# non_inv_high_pass_filter.net
KiCad netlist of a schematic drawn in EAGLE
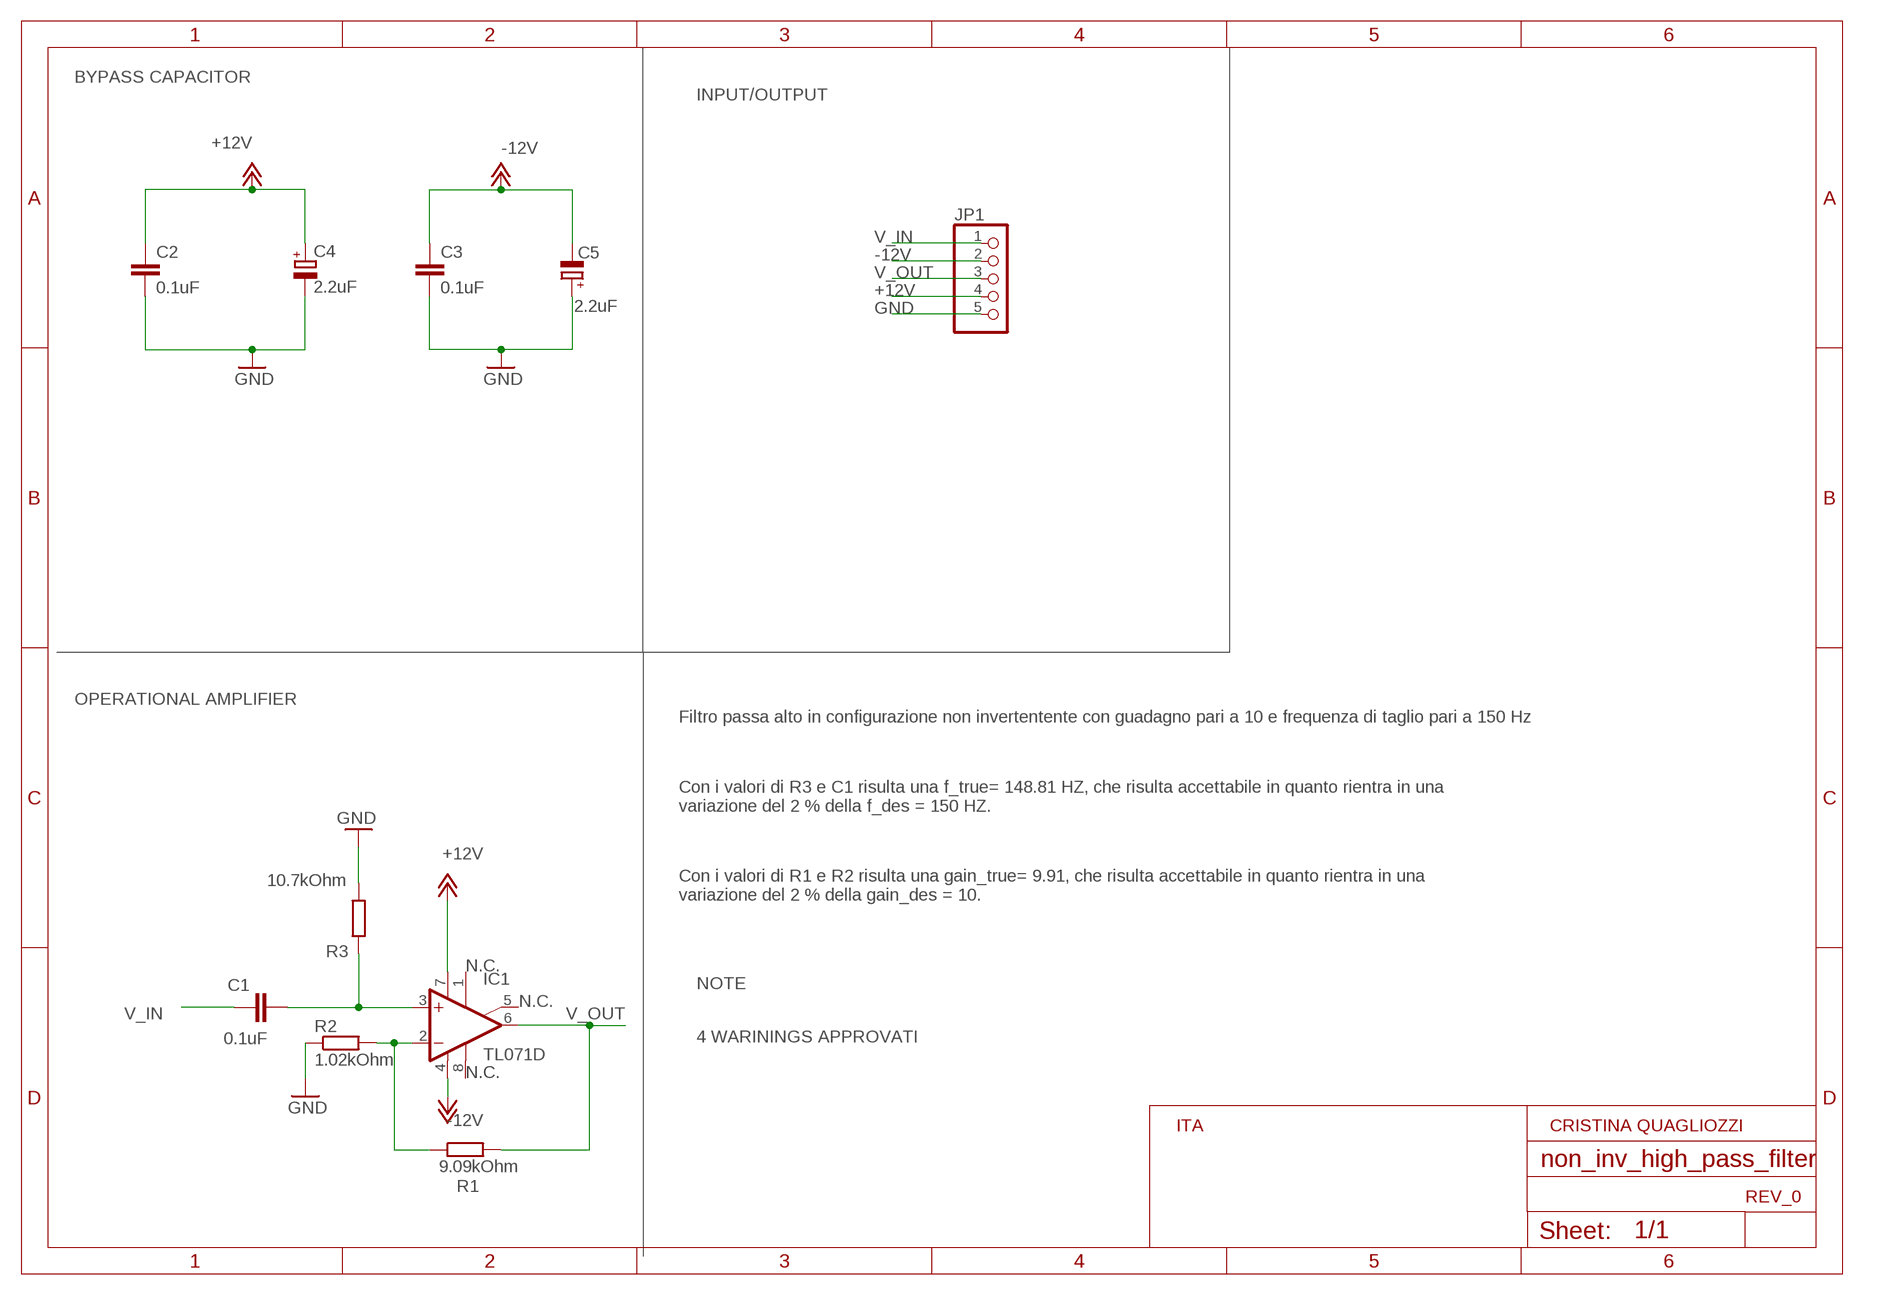
[diagram p0: schematic, sheet 1]

(export (version "E")
  (design (tool "Eeschema 10.0.6"))
  (components
    (comp (ref "C1")
      (value "0.1uF")
      (footprint "eagle-import:C0603")
      (fields (field (name "MF") "KYOCERA AVX") (field (name "MPN") "0603YC104KAT2A"))
      (libsource (lib "eagle-import") (part "C-EUC0603"))
    )
    (comp (ref "C2")
      (value "0.1uF")
      (footprint "eagle-import:C0603")
      (fields (field (name "MF") "KYOCERA AVX") (field (name "MPN") "0603YC104KAT2A"))
      (libsource (lib "eagle-import") (part "C-EUC0603"))
    )
    (comp (ref "C3")
      (value "0.1uF")
      (footprint "eagle-import:C0603")
      (fields (field (name "MF") "KYOCERA AVX") (field (name "MPN") "0603YC104KAT2A"))
      (libsource (lib "eagle-import") (part "C-EUC0603"))
    )
    (comp (ref "C4")
      (value "2.2uF")
      (footprint "eagle-import:A_3216-18R")
      (fields (field (name "MF") "KEMET") (field (name "MPN") "T491A225K016AT"))
      (libsource (lib "eagle-import") (part "CPOL-EUA/3216-18R"))
    )
    (comp (ref "C5")
      (value "2.2uF")
      (footprint "eagle-import:A_3216-18R")
      (fields (field (name "MF") "KEMET") (field (name "MPN") "T491A225K016AT"))
      (libsource (lib "eagle-import") (part "CPOL-EUA/3216-18R"))
    )
    (comp (ref "IC1")
      (value "TL071D")
      (footprint "eagle-import:SO08")
      (fields (field (name "MF") "STMICROELECTRONICS") (field (name "MPN") "TL071IDT"))
      (libsource (lib "eagle-import") (part "TL071D"))
    )
    (comp (ref "JP1")
      (value "PINHD-1X5")
      (footprint "eagle-import:1X05")
      (fields (field (name "MF") "MOLEX") (field (name "MPN") "90120-0765"))
      (libsource (lib "eagle-import") (part "PINHD-1X5"))
    )
    (comp (ref "R1")
      (value "9.09kOhm")
      (footprint "eagle-import:R0603")
      (fields (field (name "MF") "VISHAY") (field (name "MPN") "CRCW06039K09FKEA."))
      (libsource (lib "eagle-import") (part "R-EU_R0603"))
    )
    (comp (ref "R2")
      (value "1.02kOhm")
      (footprint "eagle-import:R0603")
      (fields (field (name "MF") "MULTICOMP PRO") (field (name "MPN") "MCWR06X1021FTL"))
      (libsource (lib "eagle-import") (part "R-EU_R0603"))
    )
    (comp (ref "R3")
      (value "10.7kOhm")
      (footprint "eagle-import:R0603")
      (fields (field (name "MF") "PANASONIC") (field (name "MPN") "ERJPA3F1072V"))
      (libsource (lib "eagle-import") (part "R-EU_R0603"))
    )
  )
  (nets
    (net (code "1") (name "+12V") (class "Default")
      (node (ref "C2") (pin "1") (pinfunction "1_1") (pintype "passive"))
      (node (ref "C4") (pin "+") (pinfunction "+_+") (pintype "passive"))
      (node (ref "IC1") (pin "7") (pinfunction "V+_7") (pintype "power_in"))
      (node (ref "JP1") (pin "4") (pinfunction "4_4") (pintype "passive"))
    )
    (net (code "2") (name "-12V") (class "Default")
      (node (ref "C3") (pin "1") (pinfunction "1_1") (pintype "passive"))
      (node (ref "C5") (pin "-") (pinfunction "-_-") (pintype "passive"))
      (node (ref "IC1") (pin "4") (pinfunction "V-_4") (pintype "power_in"))
      (node (ref "JP1") (pin "2") (pinfunction "2_2") (pintype "passive"))
    )
    (net (code "3") (name "/V_IN") (class "Default")
      (node (ref "C1") (pin "1") (pinfunction "1_1") (pintype "passive"))
      (node (ref "JP1") (pin "1") (pinfunction "1_1") (pintype "passive"))
    )
    (net (code "4") (name "/V_OUT") (class "Default")
      (node (ref "IC1") (pin "6") (pinfunction "OUT_6") (pintype "output"))
      (node (ref "JP1") (pin "3") (pinfunction "3_3") (pintype "passive"))
      (node (ref "R1") (pin "2") (pinfunction "2_2") (pintype "passive"))
    )
    (net (code "5") (name "GND") (class "Default")
      (node (ref "C2") (pin "2") (pinfunction "2_2") (pintype "passive"))
      (node (ref "C3") (pin "2") (pinfunction "2_2") (pintype "passive"))
      (node (ref "C4") (pin "-") (pinfunction "-_-") (pintype "passive"))
      (node (ref "C5") (pin "+") (pinfunction "+_+") (pintype "passive"))
      (node (ref "JP1") (pin "5") (pinfunction "5_5") (pintype "passive"))
      (node (ref "R2") (pin "1") (pinfunction "1_1") (pintype "passive"))
      (node (ref "R3") (pin "2") (pinfunction "2_2") (pintype "passive"))
    )
    (net (code "6") (name "Net-(IC1-+IN)") (class "Default")
      (node (ref "C1") (pin "2") (pinfunction "2_2") (pintype "passive"))
      (node (ref "IC1") (pin "3") (pinfunction "+IN_3") (pintype "input"))
      (node (ref "R3") (pin "1") (pinfunction "1_1") (pintype "passive"))
    )
    (net (code "7") (name "Net-(IC1--IN)") (class "Default")
      (node (ref "IC1") (pin "2") (pinfunction "-IN_2") (pintype "input"))
      (node (ref "R1") (pin "1") (pinfunction "1_1") (pintype "passive"))
      (node (ref "R2") (pin "2") (pinfunction "2_2") (pintype "passive"))
    )
    (net (code "8") (name "unconnected-(IC1-ON1-Pad1)") (class "Default")
      (node (ref "IC1") (pin "1") (pinfunction "ON1_1") (pintype "passive"))
    )
    (net (code "9") (name "unconnected-(IC1-ON2-Pad5)") (class "Default")
      (node (ref "IC1") (pin "5") (pinfunction "ON2_5") (pintype "passive"))
    )
    (net (code "10") (name "unconnected-(IC1-OPT-Pad8)") (class "Default")
      (node (ref "IC1") (pin "8") (pinfunction "OPT_8") (pintype "passive"))
    )
  )
)
